# SCH_Alchemist_Project_MCU_Circuit_Ver2_2.net
KiCad netlist of a schematic drawn in EasyEDA
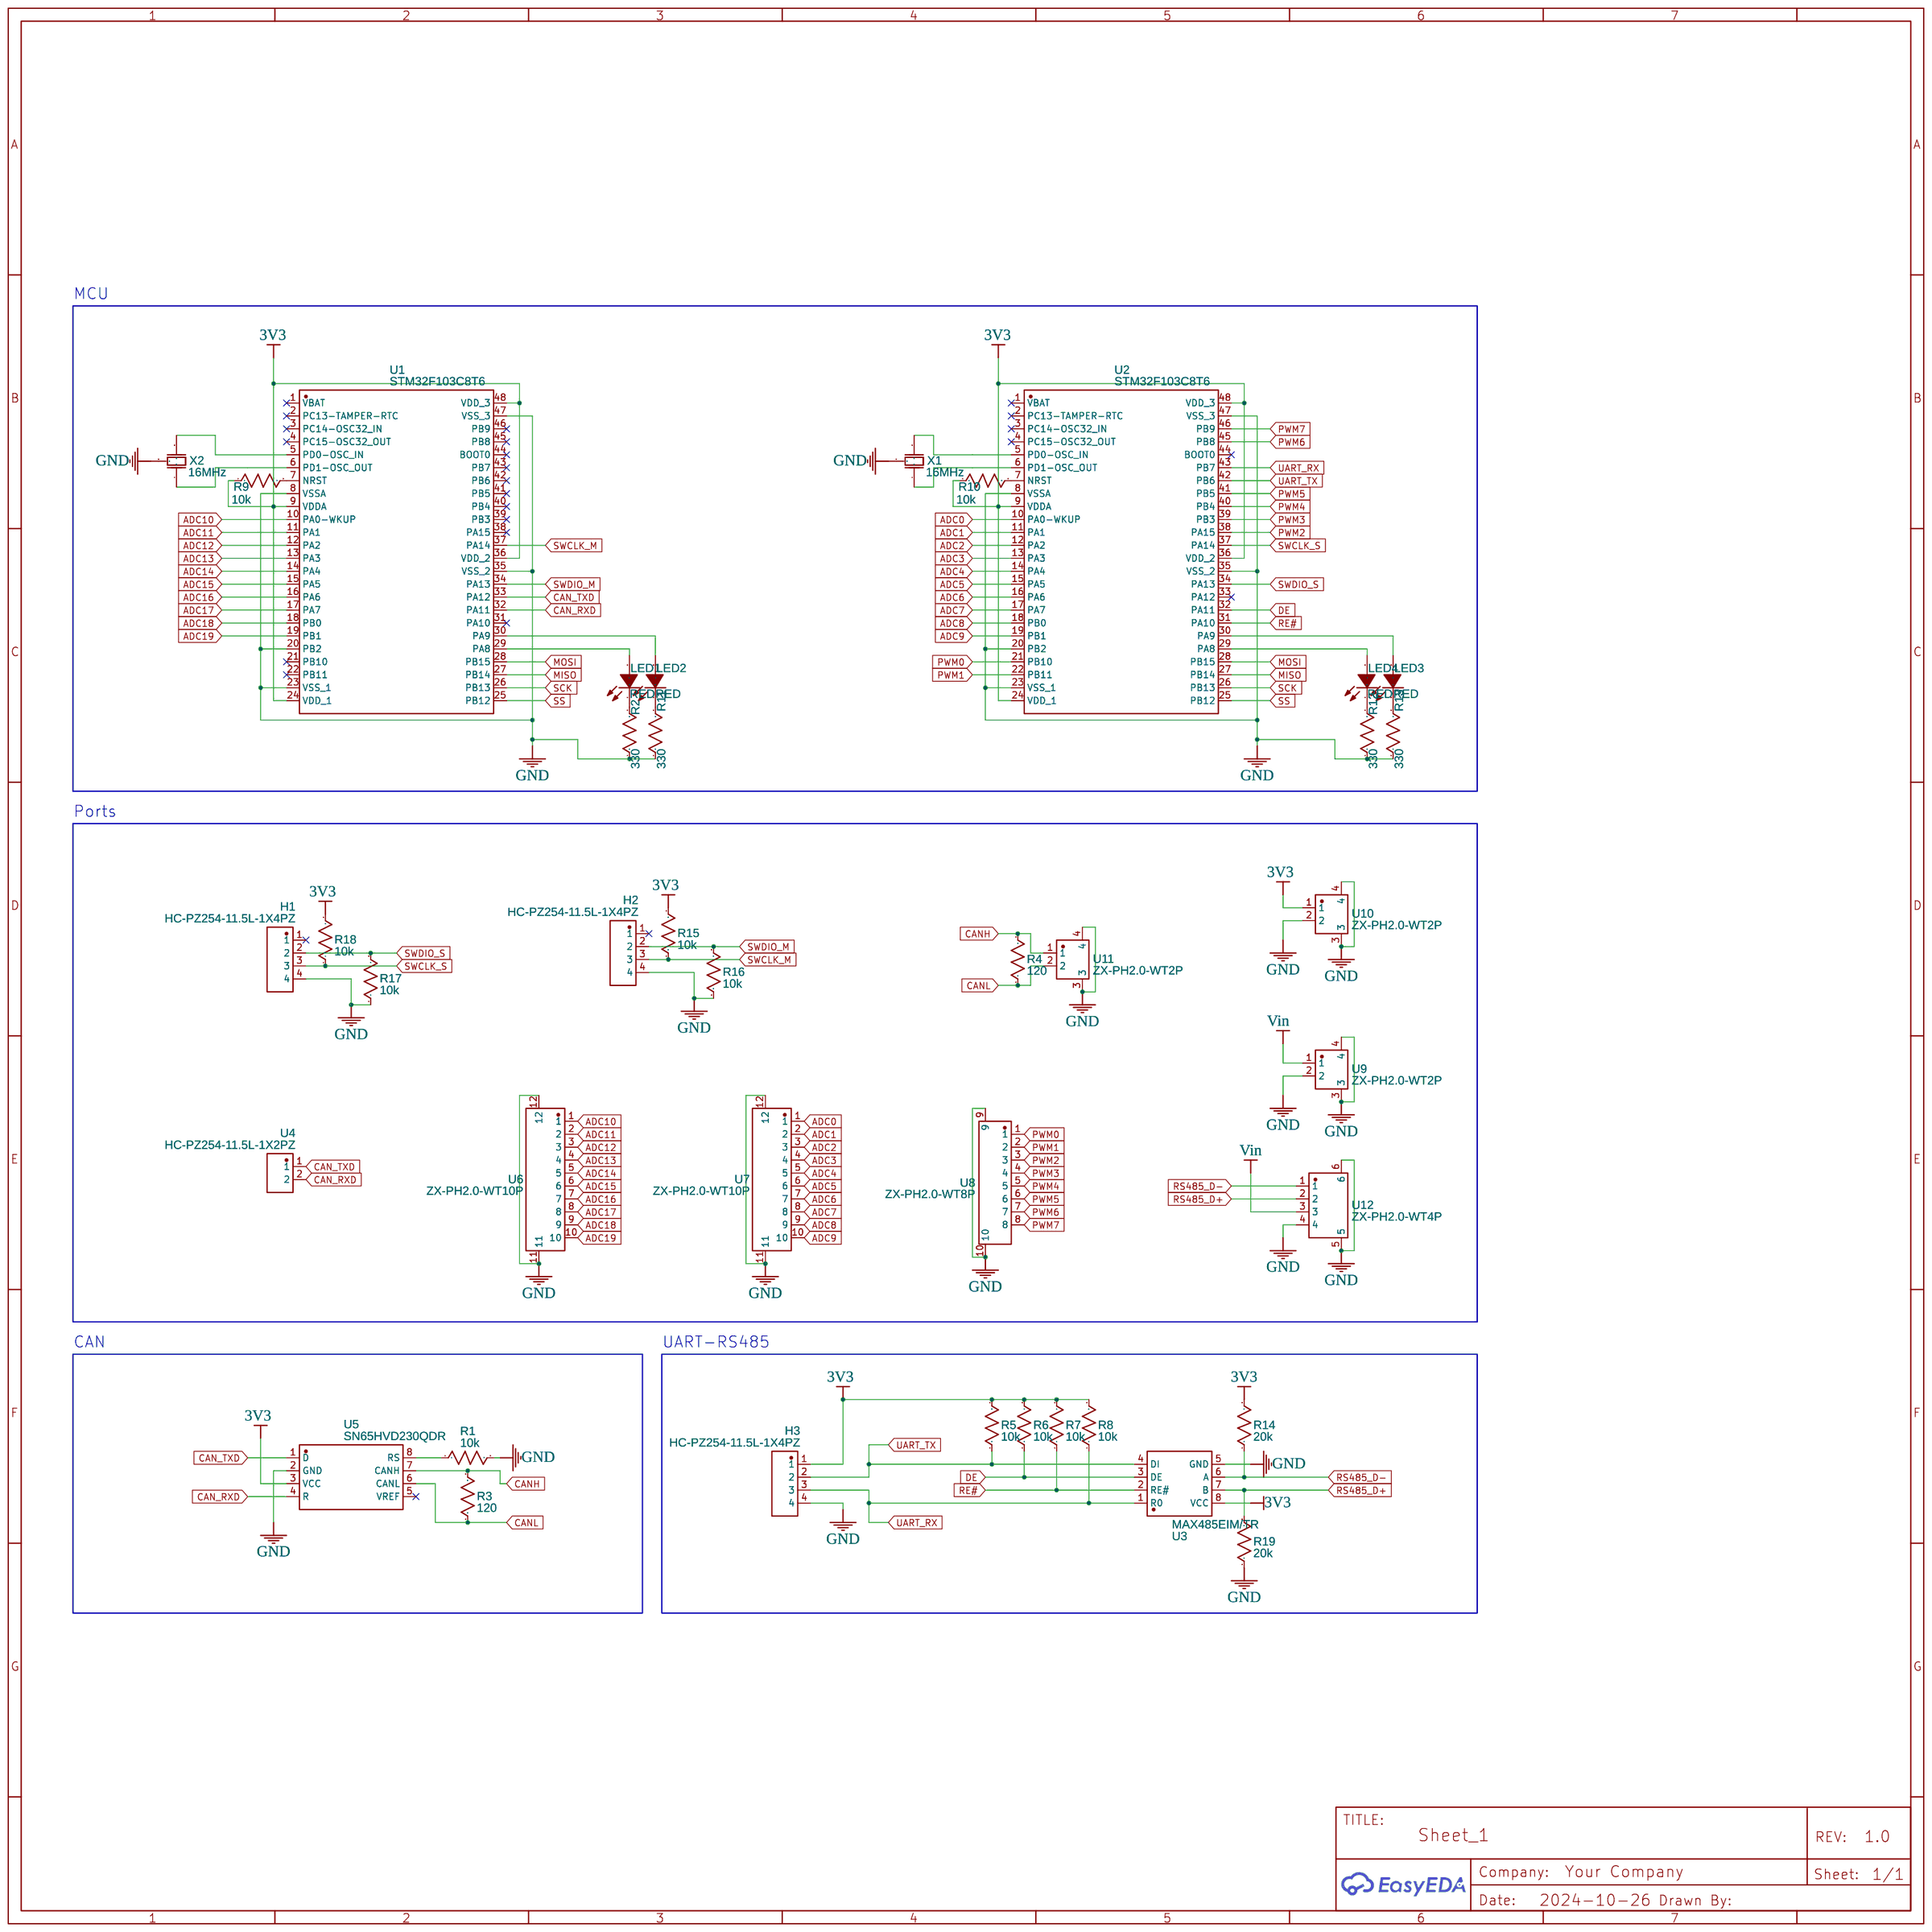
[diagram p0: schematic sheet]

(export (version "E")
  (design (tool "Eeschema 10.0.6"))
  (components
    (comp (ref "H1")
      (value "HC-PZ254-11.5L-1X4PZ")
      (fields
        (field (name "Manufacturer Part") "HC-PZ254-11.5L-1x4PZ")
        (field (name "Manufacturer") "HC(虹成电子)")
      )
      (libsource (lib "") (part "HC-PZ254-11.5L-1X4PZ"))
    )
    (comp (ref "H2")
      (value "HC-PZ254-11.5L-1X4PZ")
      (fields
        (field (name "Manufacturer Part") "HC-PZ254-11.5L-1x4PZ")
        (field (name "Manufacturer") "HC(虹成电子)")
      )
      (libsource (lib "") (part "HC-PZ254-11.5L-1X4PZ"))
    )
    (comp (ref "H3")
      (value "HC-PZ254-11.5L-1X4PZ")
      (fields
        (field (name "Manufacturer Part") "HC-PZ254-11.5L-1x4PZ")
        (field (name "Manufacturer") "HC(虹成电子)")
      )
      (libsource (lib "") (part "HC-PZ254-11.5L-1X4PZ"))
    )
    (comp (ref "LED1")
      (value "RED")
      (fields (field (name "Manufacturer Part") "KT-0603R") (field (name "Manufacturer") "KENTO"))
      (libsource (lib "") (part "KT-0603R"))
    )
    (comp (ref "LED2")
      (value "RED")
      (fields (field (name "Manufacturer Part") "KT-0603R") (field (name "Manufacturer") "KENTO"))
      (libsource (lib "") (part "KT-0603R"))
    )
    (comp (ref "LED3")
      (value "RED")
      (fields (field (name "Manufacturer Part") "KT-0603R") (field (name "Manufacturer") "KENTO"))
      (libsource (lib "") (part "KT-0603R"))
    )
    (comp (ref "LED4")
      (value "RED")
      (fields (field (name "Manufacturer Part") "KT-0603R") (field (name "Manufacturer") "KENTO"))
      (libsource (lib "") (part "KT-0603R"))
    )
    (comp (ref "R1") (value "10k") (libsource (lib "") (part "R_0603_US_1")))
    (comp (ref "R2") (value "330") (libsource (lib "") (part "R_0603_US")))
    (comp (ref "R3") (value "120") (libsource (lib "") (part "R_0603_US")))
    (comp (ref "R4") (value "120") (libsource (lib "") (part "R_0603_US")))
    (comp (ref "R5") (value "10k") (libsource (lib "") (part "R_0603_US")))
    (comp (ref "R6") (value "10k") (libsource (lib "") (part "R_0603_US")))
    (comp (ref "R7") (value "10k") (libsource (lib "") (part "R_0603_US")))
    (comp (ref "R8") (value "10k") (libsource (lib "") (part "R_0603_US")))
    (comp (ref "R9") (value "10k") (libsource (lib "") (part "R_0603_US_1")))
    (comp (ref "R10") (value "10k") (libsource (lib "") (part "R_0603_US_1")))
    (comp (ref "R11") (value "330") (libsource (lib "") (part "R_0603_US")))
    (comp (ref "R12") (value "330") (libsource (lib "") (part "R_0603_US")))
    (comp (ref "R13") (value "330") (libsource (lib "") (part "R_0603_US")))
    (comp (ref "R14") (value "20k") (libsource (lib "") (part "R_0603_US")))
    (comp (ref "R15") (value "10k") (libsource (lib "") (part "R_0603_US")))
    (comp (ref "R16") (value "10k") (libsource (lib "") (part "R_0603_US")))
    (comp (ref "R17") (value "10k") (libsource (lib "") (part "R_0603_US")))
    (comp (ref "R18") (value "10k") (libsource (lib "") (part "R_0603_US")))
    (comp (ref "R19") (value "20k") (libsource (lib "") (part "R_0603_US")))
    (comp (ref "U1")
      (value "STM32F103C8T6")
      (fields (field (name "Manufacturer") "ST(意法半导体)"))
      (libsource (lib "") (part "STM32F103C8T6"))
    )
    (comp (ref "U2")
      (value "STM32F103C8T6")
      (fields (field (name "Manufacturer") "ST(意法半导体)"))
      (libsource (lib "") (part "STM32F103C8T6"))
    )
    (comp (ref "U3")
      (value "MAX485EIM/TR")
      (fields (field (name "Manufacturer") "HGSEMI(华冠)"))
      (libsource (lib "") (part "MAX485EIM/TR"))
    )
    (comp (ref "U4")
      (value "HC-PZ254-11.5L-1X2PZ")
      (fields
        (field (name "Manufacturer Part") "HC-PZ254-11.5L-1x2PZ")
        (field (name "Manufacturer") "HC(虹成电子)")
      )
      (libsource (lib "") (part "HC-PZ254-11.5L-1X2PZ"))
    )
    (comp (ref "U5")
      (value "SN65HVD230QDR")
      (fields (field (name "Manufacturer") "TI(德州仪器)"))
      (libsource (lib "") (part "SN65HVD230QDR"))
    )
    (comp (ref "U6")
      (value "ZX-PH2.0-WT10P")
      (fields (field (name "Manufacturer") "Megastar(兆星)"))
      (libsource (lib "") (part "ZX-PH2.0-WT10P"))
    )
    (comp (ref "U7")
      (value "ZX-PH2.0-WT10P")
      (fields (field (name "Manufacturer") "Megastar(兆星)"))
      (libsource (lib "") (part "ZX-PH2.0-WT10P"))
    )
    (comp (ref "U8")
      (value "ZX-PH2.0-WT8P")
      (fields (field (name "Manufacturer") "Megastar(兆星)"))
      (libsource (lib "") (part "ZX-PH2.0-WT8P"))
    )
    (comp (ref "U9")
      (value "ZX-PH2.0-WT2P")
      (fields (field (name "Manufacturer") "Megastar(兆星)"))
      (libsource (lib "") (part "ZX-PH2.0-WT2P"))
    )
    (comp (ref "U10")
      (value "ZX-PH2.0-WT2P")
      (fields (field (name "Manufacturer") "Megastar(兆星)"))
      (libsource (lib "") (part "ZX-PH2.0-WT2P"))
    )
    (comp (ref "U11")
      (value "ZX-PH2.0-WT2P")
      (fields (field (name "Manufacturer") "Megastar(兆星)"))
      (libsource (lib "") (part "ZX-PH2.0-WT2P"))
    )
    (comp (ref "U12")
      (value "ZX-PH2.0-WT4P")
      (fields (field (name "Manufacturer") "Megastar(兆星)"))
      (libsource (lib "") (part "ZX-PH2.0-WT4P"))
    )
    (comp (ref "X1")
      (value "16MHz")
      (fields
        (field (name "Manufacturer Part") "CSTNE16M0V53C000R0")
        (field (name "Manufacturer") "muRata(村田)")
      )
      (libsource (lib "") (part "CSTNE16M0V53C000R0"))
    )
    (comp (ref "X2")
      (value "16MHz")
      (fields
        (field (name "Manufacturer Part") "CSTNE16M0V53C000R0")
        (field (name "Manufacturer") "muRata(村田)")
      )
      (libsource (lib "") (part "CSTNE16M0V53C000R0"))
    )
  )
  (nets
    (net (code "1") (name "3V3") (class "Default")
      (node (ref "H3") (pin "1") (pinfunction "1_1") (pintype "unspecified"))
      (node (ref "R10") (pin "1") (pinfunction "1_1") (pintype "unspecified"))
      (node (ref "R14") (pin "2") (pinfunction "2_2") (pintype "unspecified"))
      (node (ref "R15") (pin "2") (pinfunction "2_2") (pintype "unspecified"))
      (node (ref "R18") (pin "2") (pinfunction "2_2") (pintype "unspecified"))
      (node (ref "R5") (pin "2") (pinfunction "2_2") (pintype "unspecified"))
      (node (ref "R6") (pin "2") (pinfunction "2_2") (pintype "unspecified"))
      (node (ref "R7") (pin "2") (pinfunction "2_2") (pintype "unspecified"))
      (node (ref "R8") (pin "2") (pinfunction "2_2") (pintype "unspecified"))
      (node (ref "R9") (pin "1") (pinfunction "1_1") (pintype "unspecified"))
      (node (ref "U1") (pin "24") (pinfunction "VDD_1_24") (pintype "unspecified"))
      (node (ref "U1") (pin "36") (pinfunction "VDD_2_36") (pintype "unspecified"))
      (node (ref "U1") (pin "48") (pinfunction "VDD_3_48") (pintype "unspecified"))
      (node (ref "U1") (pin "9") (pinfunction "VDDA_9") (pintype "unspecified"))
      (node (ref "U10") (pin "1") (pinfunction "1_1") (pintype "unspecified"))
      (node (ref "U2") (pin "24") (pinfunction "VDD_1_24") (pintype "unspecified"))
      (node (ref "U2") (pin "36") (pinfunction "VDD_2_36") (pintype "unspecified"))
      (node (ref "U2") (pin "48") (pinfunction "VDD_3_48") (pintype "unspecified"))
      (node (ref "U2") (pin "9") (pinfunction "VDDA_9") (pintype "unspecified"))
      (node (ref "U3") (pin "8") (pinfunction "VCC_8") (pintype "unspecified"))
      (node (ref "U5") (pin "3") (pinfunction "VCC_3") (pintype "unspecified"))
    )
    (net (code "2") (name "ADC0") (class "Default")
      (node (ref "U2") (pin "10") (pinfunction "PA0-WKUP_10") (pintype "unspecified"))
      (node (ref "U7") (pin "1") (pinfunction "1_1") (pintype "unspecified"))
    )
    (net (code "3") (name "ADC1") (class "Default")
      (node (ref "U2") (pin "11") (pinfunction "PA1_11") (pintype "unspecified"))
      (node (ref "U7") (pin "2") (pinfunction "2_2") (pintype "unspecified"))
    )
    (net (code "4") (name "ADC2") (class "Default")
      (node (ref "U2") (pin "12") (pinfunction "PA2_12") (pintype "unspecified"))
      (node (ref "U7") (pin "3") (pinfunction "3_3") (pintype "unspecified"))
    )
    (net (code "5") (name "ADC3") (class "Default")
      (node (ref "U2") (pin "13") (pinfunction "PA3_13") (pintype "unspecified"))
      (node (ref "U7") (pin "4") (pinfunction "4_4") (pintype "unspecified"))
    )
    (net (code "6") (name "ADC4") (class "Default")
      (node (ref "U2") (pin "14") (pinfunction "PA4_14") (pintype "unspecified"))
      (node (ref "U7") (pin "5") (pinfunction "5_5") (pintype "unspecified"))
    )
    (net (code "7") (name "ADC5") (class "Default")
      (node (ref "U2") (pin "15") (pinfunction "PA5_15") (pintype "unspecified"))
      (node (ref "U7") (pin "6") (pinfunction "6_6") (pintype "unspecified"))
    )
    (net (code "8") (name "ADC6") (class "Default")
      (node (ref "U2") (pin "16") (pinfunction "PA6_16") (pintype "unspecified"))
      (node (ref "U7") (pin "7") (pinfunction "7_7") (pintype "unspecified"))
    )
    (net (code "9") (name "ADC7") (class "Default")
      (node (ref "U2") (pin "17") (pinfunction "PA7_17") (pintype "unspecified"))
      (node (ref "U7") (pin "8") (pinfunction "8_8") (pintype "unspecified"))
    )
    (net (code "10") (name "ADC8") (class "Default")
      (node (ref "U2") (pin "18") (pinfunction "PB0_18") (pintype "unspecified"))
      (node (ref "U7") (pin "9") (pinfunction "9_9") (pintype "unspecified"))
    )
    (net (code "11") (name "ADC9") (class "Default")
      (node (ref "U2") (pin "19") (pinfunction "PB1_19") (pintype "unspecified"))
      (node (ref "U7") (pin "10") (pinfunction "10_10") (pintype "unspecified"))
    )
    (net (code "12") (name "ADC10") (class "Default")
      (node (ref "U1") (pin "10") (pinfunction "PA0-WKUP_10") (pintype "unspecified"))
      (node (ref "U6") (pin "1") (pinfunction "1_1") (pintype "unspecified"))
    )
    (net (code "13") (name "ADC11") (class "Default")
      (node (ref "U1") (pin "11") (pinfunction "PA1_11") (pintype "unspecified"))
      (node (ref "U6") (pin "2") (pinfunction "2_2") (pintype "unspecified"))
    )
    (net (code "14") (name "ADC12") (class "Default")
      (node (ref "U1") (pin "12") (pinfunction "PA2_12") (pintype "unspecified"))
      (node (ref "U6") (pin "3") (pinfunction "3_3") (pintype "unspecified"))
    )
    (net (code "15") (name "ADC13") (class "Default")
      (node (ref "U1") (pin "13") (pinfunction "PA3_13") (pintype "unspecified"))
      (node (ref "U6") (pin "4") (pinfunction "4_4") (pintype "unspecified"))
    )
    (net (code "16") (name "ADC14") (class "Default")
      (node (ref "U1") (pin "14") (pinfunction "PA4_14") (pintype "unspecified"))
      (node (ref "U6") (pin "5") (pinfunction "5_5") (pintype "unspecified"))
    )
    (net (code "17") (name "ADC15") (class "Default")
      (node (ref "U1") (pin "15") (pinfunction "PA5_15") (pintype "unspecified"))
      (node (ref "U6") (pin "6") (pinfunction "6_6") (pintype "unspecified"))
    )
    (net (code "18") (name "ADC16") (class "Default")
      (node (ref "U1") (pin "16") (pinfunction "PA6_16") (pintype "unspecified"))
      (node (ref "U6") (pin "7") (pinfunction "7_7") (pintype "unspecified"))
    )
    (net (code "19") (name "ADC17") (class "Default")
      (node (ref "U1") (pin "17") (pinfunction "PA7_17") (pintype "unspecified"))
      (node (ref "U6") (pin "8") (pinfunction "8_8") (pintype "unspecified"))
    )
    (net (code "20") (name "ADC18") (class "Default")
      (node (ref "U1") (pin "18") (pinfunction "PB0_18") (pintype "unspecified"))
      (node (ref "U6") (pin "9") (pinfunction "9_9") (pintype "unspecified"))
    )
    (net (code "21") (name "ADC19") (class "Default")
      (node (ref "U1") (pin "19") (pinfunction "PB1_19") (pintype "unspecified"))
      (node (ref "U6") (pin "10") (pinfunction "10_10") (pintype "unspecified"))
    )
    (net (code "22") (name "CANH") (class "Default")
      (node (ref "R3") (pin "2") (pinfunction "2_2") (pintype "unspecified"))
      (node (ref "R4") (pin "2") (pinfunction "2_2") (pintype "unspecified"))
      (node (ref "U11") (pin "1") (pinfunction "1_1") (pintype "unspecified"))
      (node (ref "U5") (pin "7") (pinfunction "CANH_7") (pintype "unspecified"))
    )
    (net (code "23") (name "CANL") (class "Default")
      (node (ref "R3") (pin "1") (pinfunction "1_1") (pintype "unspecified"))
      (node (ref "R4") (pin "1") (pinfunction "1_1") (pintype "unspecified"))
      (node (ref "U11") (pin "2") (pinfunction "2_2") (pintype "unspecified"))
      (node (ref "U5") (pin "6") (pinfunction "CANL_6") (pintype "unspecified"))
    )
    (net (code "24") (name "CAN_RXD") (class "Default")
      (node (ref "U1") (pin "32") (pinfunction "PA11_32") (pintype "unspecified"))
      (node (ref "U4") (pin "2") (pinfunction "2_2") (pintype "unspecified"))
      (node (ref "U5") (pin "4") (pinfunction "R_4") (pintype "unspecified"))
    )
    (net (code "25") (name "CAN_TXD") (class "Default")
      (node (ref "U1") (pin "33") (pinfunction "PA12_33") (pintype "unspecified"))
      (node (ref "U4") (pin "1") (pinfunction "1_1") (pintype "unspecified"))
      (node (ref "U5") (pin "1") (pinfunction "D_1") (pintype "unspecified"))
    )
    (net (code "26") (name "DE") (class "Default")
      (node (ref "R6") (pin "1") (pinfunction "1_1") (pintype "unspecified"))
      (node (ref "U2") (pin "32") (pinfunction "PA11_32") (pintype "unspecified"))
      (node (ref "U3") (pin "3") (pinfunction "DE_3") (pintype "unspecified"))
    )
    (net (code "27") (name "GND") (class "Default")
      (node (ref "H1") (pin "4") (pinfunction "4_4") (pintype "unspecified"))
      (node (ref "H2") (pin "4") (pinfunction "4_4") (pintype "unspecified"))
      (node (ref "H3") (pin "4") (pinfunction "4_4") (pintype "unspecified"))
      (node (ref "R1") (pin "2") (pinfunction "2_2") (pintype "unspecified"))
      (node (ref "R11") (pin "1") (pinfunction "1_1") (pintype "unspecified"))
      (node (ref "R12") (pin "1") (pinfunction "1_1") (pintype "unspecified"))
      (node (ref "R13") (pin "1") (pinfunction "1_1") (pintype "unspecified"))
      (node (ref "R16") (pin "1") (pinfunction "1_1") (pintype "unspecified"))
      (node (ref "R17") (pin "1") (pinfunction "1_1") (pintype "unspecified"))
      (node (ref "R19") (pin "1") (pinfunction "1_1") (pintype "unspecified"))
      (node (ref "R2") (pin "1") (pinfunction "1_1") (pintype "unspecified"))
      (node (ref "U1") (pin "20") (pinfunction "PB2_20") (pintype "unspecified"))
      (node (ref "U1") (pin "23") (pinfunction "VSS_1_23") (pintype "unspecified"))
      (node (ref "U1") (pin "35") (pinfunction "VSS_2_35") (pintype "unspecified"))
      (node (ref "U1") (pin "47") (pinfunction "VSS_3_47") (pintype "unspecified"))
      (node (ref "U1") (pin "8") (pinfunction "VSSA_8") (pintype "unspecified"))
      (node (ref "U10") (pin "2") (pinfunction "2_2") (pintype "unspecified"))
      (node (ref "U10") (pin "3") (pinfunction "3_3") (pintype "unspecified"))
      (node (ref "U10") (pin "4") (pinfunction "4_4") (pintype "unspecified"))
      (node (ref "U11") (pin "3") (pinfunction "3_3") (pintype "unspecified"))
      (node (ref "U11") (pin "4") (pinfunction "4_4") (pintype "unspecified"))
      (node (ref "U12") (pin "4") (pinfunction "4_4") (pintype "unspecified"))
      (node (ref "U12") (pin "5") (pinfunction "5_5") (pintype "unspecified"))
      (node (ref "U12") (pin "6") (pinfunction "6_6") (pintype "unspecified"))
      (node (ref "U2") (pin "20") (pinfunction "PB2_20") (pintype "unspecified"))
      (node (ref "U2") (pin "23") (pinfunction "VSS_1_23") (pintype "unspecified"))
      (node (ref "U2") (pin "35") (pinfunction "VSS_2_35") (pintype "unspecified"))
      (node (ref "U2") (pin "47") (pinfunction "VSS_3_47") (pintype "unspecified"))
      (node (ref "U2") (pin "8") (pinfunction "VSSA_8") (pintype "unspecified"))
      (node (ref "U3") (pin "5") (pinfunction "GND_5") (pintype "unspecified"))
      (node (ref "U5") (pin "2") (pinfunction "GND_2") (pintype "unspecified"))
      (node (ref "U6") (pin "11") (pinfunction "11_11") (pintype "unspecified"))
      (node (ref "U6") (pin "12") (pinfunction "12_12") (pintype "unspecified"))
      (node (ref "U7") (pin "11") (pinfunction "11_11") (pintype "unspecified"))
      (node (ref "U7") (pin "12") (pinfunction "12_12") (pintype "unspecified"))
      (node (ref "U8") (pin "10") (pinfunction "10_10") (pintype "unspecified"))
      (node (ref "U8") (pin "9") (pinfunction "9_9") (pintype "unspecified"))
      (node (ref "U9") (pin "2") (pinfunction "2_2") (pintype "unspecified"))
      (node (ref "U9") (pin "3") (pinfunction "3_3") (pintype "unspecified"))
      (node (ref "U9") (pin "4") (pinfunction "4_4") (pintype "unspecified"))
      (node (ref "X1") (pin "2") (pinfunction "GND_2") (pintype "input"))
      (node (ref "X2") (pin "2") (pinfunction "GND_2") (pintype "input"))
    )
    (net (code "28") (name "MISO") (class "Default")
      (node (ref "U1") (pin "27") (pinfunction "PB14_27") (pintype "unspecified"))
      (node (ref "U2") (pin "27") (pinfunction "PB14_27") (pintype "unspecified"))
    )
    (net (code "29") (name "MOSI") (class "Default")
      (node (ref "U1") (pin "28") (pinfunction "PB15_28") (pintype "unspecified"))
      (node (ref "U2") (pin "28") (pinfunction "PB15_28") (pintype "unspecified"))
    )
    (net (code "30") (name "Net-(LED1-A)") (class "Default")
      (node (ref "LED1") (pin "2") (pinfunction "A_2") (pintype "unspecified"))
      (node (ref "U1") (pin "29") (pinfunction "PA8_29") (pintype "unspecified"))
    )
    (net (code "31") (name "Net-(LED1-K)") (class "Default")
      (node (ref "LED1") (pin "1") (pinfunction "K_1") (pintype "unspecified"))
      (node (ref "R2") (pin "2") (pinfunction "2_2") (pintype "unspecified"))
    )
    (net (code "32") (name "Net-(LED2-A)") (class "Default")
      (node (ref "LED2") (pin "2") (pinfunction "A_2") (pintype "unspecified"))
      (node (ref "U1") (pin "30") (pinfunction "PA9_30") (pintype "unspecified"))
    )
    (net (code "33") (name "Net-(LED2-K)") (class "Default")
      (node (ref "LED2") (pin "1") (pinfunction "K_1") (pintype "unspecified"))
      (node (ref "R11") (pin "2") (pinfunction "2_2") (pintype "unspecified"))
    )
    (net (code "34") (name "Net-(LED3-A)") (class "Default")
      (node (ref "LED3") (pin "2") (pinfunction "A_2") (pintype "unspecified"))
      (node (ref "U2") (pin "30") (pinfunction "PA9_30") (pintype "unspecified"))
    )
    (net (code "35") (name "Net-(LED3-K)") (class "Default")
      (node (ref "LED3") (pin "1") (pinfunction "K_1") (pintype "unspecified"))
      (node (ref "R13") (pin "2") (pinfunction "2_2") (pintype "unspecified"))
    )
    (net (code "36") (name "Net-(LED4-A)") (class "Default")
      (node (ref "LED4") (pin "2") (pinfunction "A_2") (pintype "unspecified"))
      (node (ref "U2") (pin "29") (pinfunction "PA8_29") (pintype "unspecified"))
    )
    (net (code "37") (name "Net-(LED4-K)") (class "Default")
      (node (ref "LED4") (pin "1") (pinfunction "K_1") (pintype "unspecified"))
      (node (ref "R12") (pin "2") (pinfunction "2_2") (pintype "unspecified"))
    )
    (net (code "38") (name "Net-(U1-NRST)") (class "Default")
      (node (ref "R9") (pin "2") (pinfunction "2_2") (pintype "unspecified"))
      (node (ref "U1") (pin "7") (pinfunction "NRST_7") (pintype "unspecified"))
    )
    (net (code "39") (name "Net-(U1-PD0-OSC_IN)") (class "Default")
      (node (ref "U1") (pin "5") (pinfunction "PD0-OSC_IN_5") (pintype "unspecified"))
      (node (ref "X2") (pin "3") (pinfunction "OSC2_3") (pintype "input"))
    )
    (net (code "40") (name "Net-(U1-PD1-OSC_OUT)") (class "Default")
      (node (ref "U1") (pin "6") (pinfunction "PD1-OSC_OUT_6") (pintype "unspecified"))
      (node (ref "X2") (pin "1") (pinfunction "OSC1_1") (pintype "input"))
    )
    (net (code "41") (name "Net-(U2-NRST)") (class "Default")
      (node (ref "R10") (pin "2") (pinfunction "2_2") (pintype "unspecified"))
      (node (ref "U2") (pin "7") (pinfunction "NRST_7") (pintype "unspecified"))
    )
    (net (code "42") (name "Net-(U2-PD0-OSC_IN)") (class "Default")
      (node (ref "U2") (pin "5") (pinfunction "PD0-OSC_IN_5") (pintype "unspecified"))
      (node (ref "X1") (pin "3") (pinfunction "OSC2_3") (pintype "input"))
    )
    (net (code "43") (name "Net-(U2-PD1-OSC_OUT)") (class "Default")
      (node (ref "U2") (pin "6") (pinfunction "PD1-OSC_OUT_6") (pintype "unspecified"))
      (node (ref "X1") (pin "1") (pinfunction "OSC1_1") (pintype "input"))
    )
    (net (code "44") (name "Net-(U5-RS)") (class "Default")
      (node (ref "R1") (pin "1") (pinfunction "1_1") (pintype "unspecified"))
      (node (ref "U5") (pin "8") (pinfunction "RS_8") (pintype "unspecified"))
    )
    (net (code "45") (name "PWM0") (class "Default")
      (node (ref "U2") (pin "21") (pinfunction "PB10_21") (pintype "unspecified"))
      (node (ref "U8") (pin "1") (pinfunction "1_1") (pintype "unspecified"))
    )
    (net (code "46") (name "PWM1") (class "Default")
      (node (ref "U2") (pin "22") (pinfunction "PB11_22") (pintype "unspecified"))
      (node (ref "U8") (pin "2") (pinfunction "2_2") (pintype "unspecified"))
    )
    (net (code "47") (name "PWM2") (class "Default")
      (node (ref "U2") (pin "38") (pinfunction "PA15_38") (pintype "unspecified"))
      (node (ref "U8") (pin "3") (pinfunction "3_3") (pintype "unspecified"))
    )
    (net (code "48") (name "PWM3") (class "Default")
      (node (ref "U2") (pin "39") (pinfunction "PB3_39") (pintype "unspecified"))
      (node (ref "U8") (pin "4") (pinfunction "4_4") (pintype "unspecified"))
    )
    (net (code "49") (name "PWM4") (class "Default")
      (node (ref "U2") (pin "40") (pinfunction "PB4_40") (pintype "unspecified"))
      (node (ref "U8") (pin "5") (pinfunction "5_5") (pintype "unspecified"))
    )
    (net (code "50") (name "PWM5") (class "Default")
      (node (ref "U2") (pin "41") (pinfunction "PB5_41") (pintype "unspecified"))
      (node (ref "U8") (pin "6") (pinfunction "6_6") (pintype "unspecified"))
    )
    (net (code "51") (name "PWM6") (class "Default")
      (node (ref "U2") (pin "45") (pinfunction "PB8_45") (pintype "unspecified"))
      (node (ref "U8") (pin "7") (pinfunction "7_7") (pintype "unspecified"))
    )
    (net (code "52") (name "PWM7") (class "Default")
      (node (ref "U2") (pin "46") (pinfunction "PB9_46") (pintype "unspecified"))
      (node (ref "U8") (pin "8") (pinfunction "8_8") (pintype "unspecified"))
    )
    (net (code "53") (name "RE#") (class "Default")
      (node (ref "R7") (pin "1") (pinfunction "1_1") (pintype "unspecified"))
      (node (ref "U2") (pin "31") (pinfunction "PA10_31") (pintype "unspecified"))
      (node (ref "U3") (pin "2") (pinfunction "RE#_2") (pintype "unspecified"))
    )
    (net (code "54") (name "RS485_D+") (class "Default")
      (node (ref "R19") (pin "2") (pinfunction "2_2") (pintype "unspecified"))
      (node (ref "U12") (pin "2") (pinfunction "2_2") (pintype "unspecified"))
      (node (ref "U3") (pin "7") (pinfunction "B_7") (pintype "unspecified"))
    )
    (net (code "55") (name "RS485_D-") (class "Default")
      (node (ref "R14") (pin "1") (pinfunction "1_1") (pintype "unspecified"))
      (node (ref "U12") (pin "1") (pinfunction "1_1") (pintype "unspecified"))
      (node (ref "U3") (pin "6") (pinfunction "A_6") (pintype "unspecified"))
    )
    (net (code "56") (name "SCK") (class "Default")
      (node (ref "U1") (pin "26") (pinfunction "PB13_26") (pintype "unspecified"))
      (node (ref "U2") (pin "26") (pinfunction "PB13_26") (pintype "unspecified"))
    )
    (net (code "57") (name "SS") (class "Default")
      (node (ref "U1") (pin "25") (pinfunction "PB12_25") (pintype "unspecified"))
      (node (ref "U2") (pin "25") (pinfunction "PB12_25") (pintype "unspecified"))
    )
    (net (code "58") (name "SWCLK_M") (class "Default")
      (node (ref "H2") (pin "3") (pinfunction "3_3") (pintype "unspecified"))
      (node (ref "R15") (pin "1") (pinfunction "1_1") (pintype "unspecified"))
      (node (ref "U1") (pin "37") (pinfunction "PA14_37") (pintype "unspecified"))
    )
    (net (code "59") (name "SWCLK_S") (class "Default")
      (node (ref "H1") (pin "3") (pinfunction "3_3") (pintype "unspecified"))
      (node (ref "R18") (pin "1") (pinfunction "1_1") (pintype "unspecified"))
      (node (ref "U2") (pin "37") (pinfunction "PA14_37") (pintype "unspecified"))
    )
    (net (code "60") (name "SWDIO_M") (class "Default")
      (node (ref "H2") (pin "2") (pinfunction "2_2") (pintype "unspecified"))
      (node (ref "R16") (pin "2") (pinfunction "2_2") (pintype "unspecified"))
      (node (ref "U1") (pin "34") (pinfunction "PA13_34") (pintype "unspecified"))
    )
    (net (code "61") (name "SWDIO_S") (class "Default")
      (node (ref "H1") (pin "2") (pinfunction "2_2") (pintype "unspecified"))
      (node (ref "R17") (pin "2") (pinfunction "2_2") (pintype "unspecified"))
      (node (ref "U2") (pin "34") (pinfunction "PA13_34") (pintype "unspecified"))
    )
    (net (code "62") (name "UART_RX") (class "Default")
      (node (ref "H3") (pin "3") (pinfunction "3_3") (pintype "unspecified"))
      (node (ref "R8") (pin "1") (pinfunction "1_1") (pintype "unspecified"))
      (node (ref "U2") (pin "43") (pinfunction "PB7_43") (pintype "unspecified"))
      (node (ref "U3") (pin "1") (pinfunction "R0_1") (pintype "unspecified"))
    )
    (net (code "63") (name "UART_TX") (class "Default")
      (node (ref "H3") (pin "2") (pinfunction "2_2") (pintype "unspecified"))
      (node (ref "R5") (pin "1") (pinfunction "1_1") (pintype "unspecified"))
      (node (ref "U2") (pin "42") (pinfunction "PB6_42") (pintype "unspecified"))
      (node (ref "U3") (pin "4") (pinfunction "DI_4") (pintype "unspecified"))
    )
    (net (code "64") (name "Vin") (class "Default")
      (node (ref "U12") (pin "3") (pinfunction "3_3") (pintype "unspecified"))
      (node (ref "U9") (pin "1") (pinfunction "1_1") (pintype "unspecified"))
    )
    (net (code "65") (name "unconnected-(H1-Pad1)") (class "Default")
      (node (ref "H1") (pin "1") (pinfunction "1_1") (pintype "unspecified+no_connect"))
    )
    (net (code "66") (name "unconnected-(H2-Pad1)") (class "Default")
      (node (ref "H2") (pin "1") (pinfunction "1_1") (pintype "unspecified+no_connect"))
    )
    (net (code "67") (name "unconnected-(U1-BOOT0-Pad44)") (class "Default")
      (node (ref "U1") (pin "44") (pinfunction "BOOT0_44") (pintype "unspecified+no_connect"))
    )
    (net (code "68") (name "unconnected-(U1-PA10-Pad31)") (class "Default")
      (node (ref "U1") (pin "31") (pinfunction "PA10_31") (pintype "unspecified+no_connect"))
    )
    (net (code "69") (name "unconnected-(U1-PA15-Pad38)") (class "Default")
      (node (ref "U1") (pin "38") (pinfunction "PA15_38") (pintype "unspecified+no_connect"))
    )
    (net (code "70") (name "unconnected-(U1-PB3-Pad39)") (class "Default")
      (node (ref "U1") (pin "39") (pinfunction "PB3_39") (pintype "unspecified+no_connect"))
    )
    (net (code "71") (name "unconnected-(U1-PB4-Pad40)") (class "Default")
      (node (ref "U1") (pin "40") (pinfunction "PB4_40") (pintype "unspecified+no_connect"))
    )
    (net (code "72") (name "unconnected-(U1-PB5-Pad41)") (class "Default")
      (node (ref "U1") (pin "41") (pinfunction "PB5_41") (pintype "unspecified+no_connect"))
    )
    (net (code "73") (name "unconnected-(U1-PB6-Pad42)") (class "Default")
      (node (ref "U1") (pin "42") (pinfunction "PB6_42") (pintype "unspecified+no_connect"))
    )
    (net (code "74") (name "unconnected-(U1-PB7-Pad43)") (class "Default")
      (node (ref "U1") (pin "43") (pinfunction "PB7_43") (pintype "unspecified+no_connect"))
    )
    (net (code "75") (name "unconnected-(U1-PB8-Pad45)") (class "Default")
      (node (ref "U1") (pin "45") (pinfunction "PB8_45") (pintype "unspecified+no_connect"))
    )
    (net (code "76") (name "unconnected-(U1-PB9-Pad46)") (class "Default")
      (node (ref "U1") (pin "46") (pinfunction "PB9_46") (pintype "unspecified+no_connect"))
    )
    (net (code "77") (name "unconnected-(U1-PB10-Pad21)") (class "Default")
      (node (ref "U1") (pin "21") (pinfunction "PB10_21") (pintype "unspecified+no_connect"))
    )
    (net (code "78") (name "unconnected-(U1-PB11-Pad22)") (class "Default")
      (node (ref "U1") (pin "22") (pinfunction "PB11_22") (pintype "unspecified+no_connect"))
    )
    (net (code "79") (name "unconnected-(U1-PC13-TAMPER-RTC-Pad2)") (class "Default")
      (node (ref "U1") (pin "2") (pinfunction "PC13-TAMPER-RTC_2") (pintype "unspecified+no_connect"))
    )
    (net (code "80") (name "unconnected-(U1-PC14-OSC32_IN-Pad3)") (class "Default")
      (node (ref "U1") (pin "3") (pinfunction "PC14-OSC32_IN_3") (pintype "unspecified+no_connect"))
    )
    (net (code "81") (name "unconnected-(U1-PC15-OSC32_OUT-Pad4)") (class "Default")
      (node (ref "U1") (pin "4") (pinfunction "PC15-OSC32_OUT_4") (pintype "unspecified+no_connect"))
    )
    (net (code "82") (name "unconnected-(U1-VBAT-Pad1)") (class "Default")
      (node (ref "U1") (pin "1") (pinfunction "VBAT_1") (pintype "unspecified+no_connect"))
    )
    (net (code "83") (name "unconnected-(U2-BOOT0-Pad44)") (class "Default")
      (node (ref "U2") (pin "44") (pinfunction "BOOT0_44") (pintype "unspecified+no_connect"))
    )
    (net (code "84") (name "unconnected-(U2-PA12-Pad33)") (class "Default")
      (node (ref "U2") (pin "33") (pinfunction "PA12_33") (pintype "unspecified+no_connect"))
    )
    (net (code "85") (name "unconnected-(U2-PC13-TAMPER-RTC-Pad2)") (class "Default")
      (node (ref "U2") (pin "2") (pinfunction "PC13-TAMPER-RTC_2") (pintype "unspecified+no_connect"))
    )
    (net (code "86") (name "unconnected-(U2-PC14-OSC32_IN-Pad3)") (class "Default")
      (node (ref "U2") (pin "3") (pinfunction "PC14-OSC32_IN_3") (pintype "unspecified+no_connect"))
    )
    (net (code "87") (name "unconnected-(U2-PC15-OSC32_OUT-Pad4)") (class "Default")
      (node (ref "U2") (pin "4") (pinfunction "PC15-OSC32_OUT_4") (pintype "unspecified+no_connect"))
    )
    (net (code "88") (name "unconnected-(U2-VBAT-Pad1)") (class "Default")
      (node (ref "U2") (pin "1") (pinfunction "VBAT_1") (pintype "unspecified+no_connect"))
    )
    (net (code "89") (name "unconnected-(U5-VREF-Pad5)") (class "Default")
      (node (ref "U5") (pin "5") (pinfunction "VREF_5") (pintype "unspecified+no_connect"))
    )
  )
)
